# sensor_pcb_3.net
KiCad netlist of a schematic drawn in EAGLE
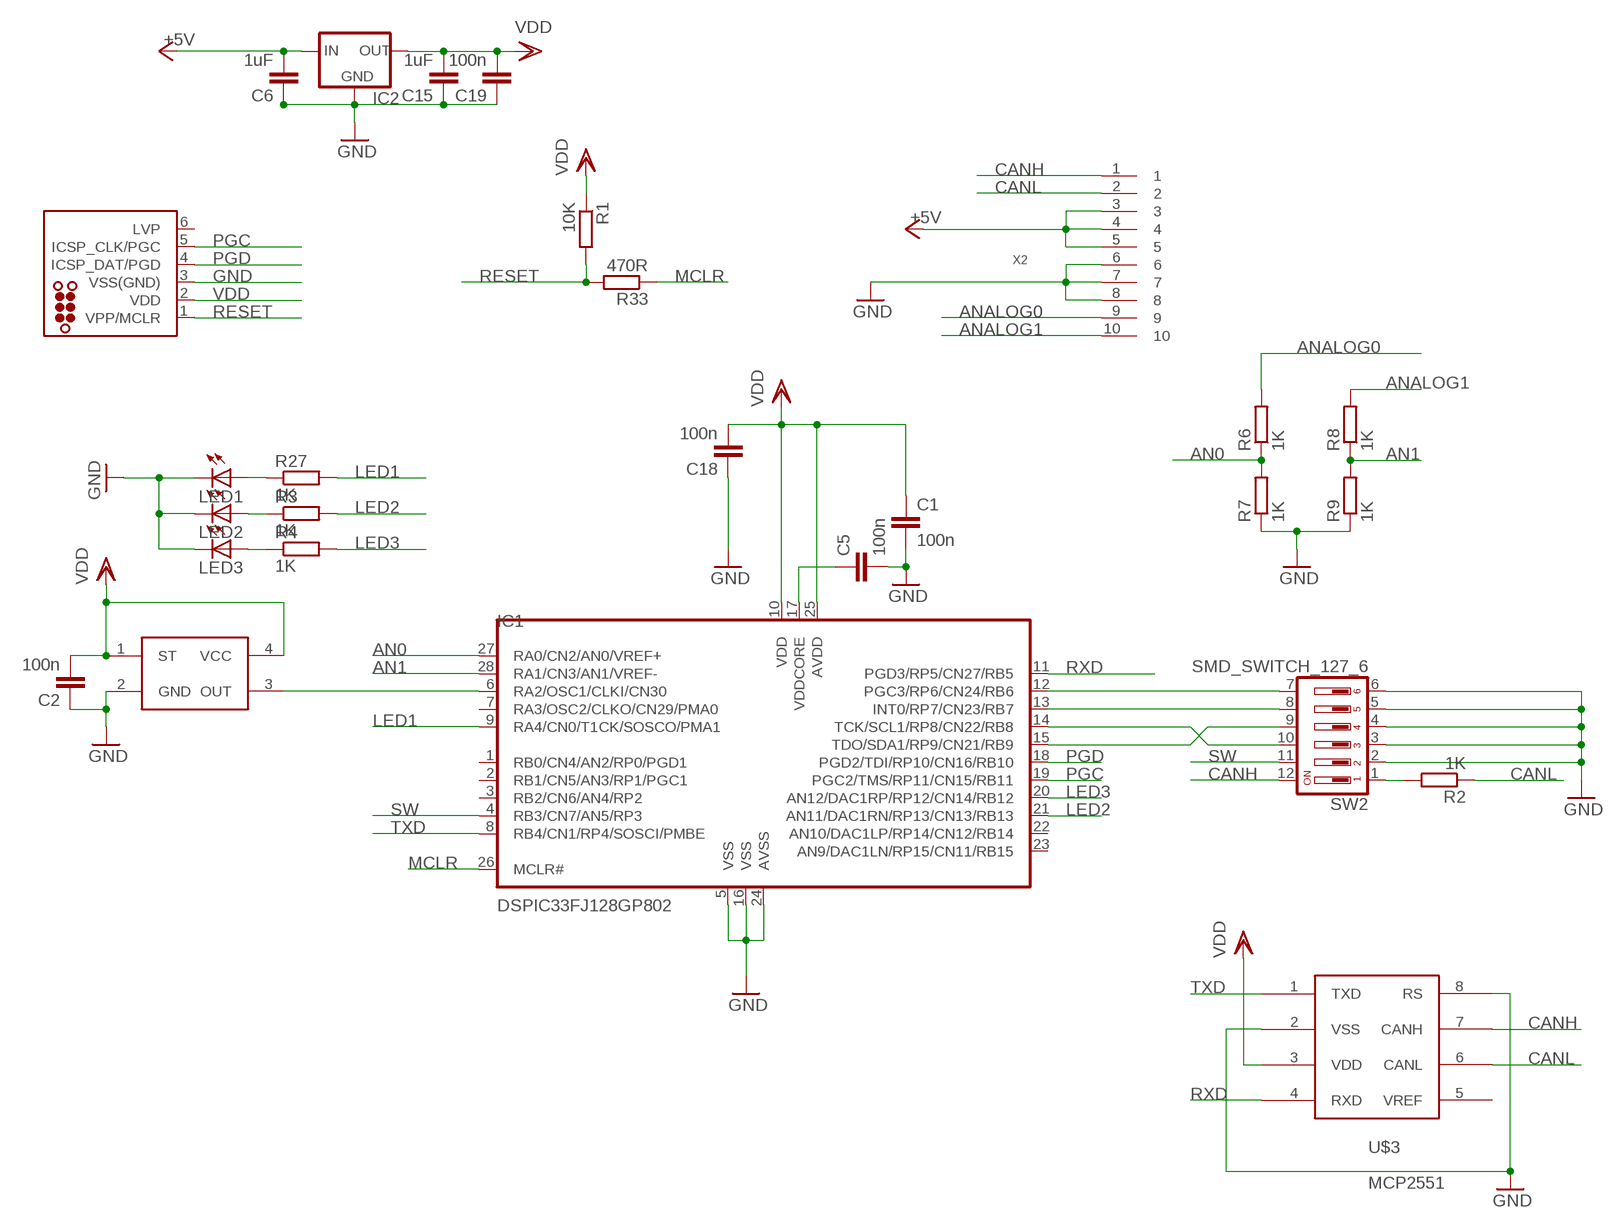
[diagram p0: schematic, sheet 1]

(export (version "E")
  (design (tool "Eeschema 10.0.6"))
  (components
    (comp (ref "C1")
      (value "100n")
      (footprint "eagle-import:C0402K")
      (libsource (lib "eagle-import") (part "C-EUC0402K"))
    )
    (comp (ref "C2")
      (value "100n")
      (footprint "eagle-import:C0402K")
      (libsource (lib "eagle-import") (part "C-EUC0402K"))
    )
    (comp (ref "C5")
      (value "100n")
      (footprint "eagle-import:C0402K")
      (libsource (lib "eagle-import") (part "C-EUC0402K"))
    )
    (comp (ref "C6")
      (value "1uF")
      (footprint "eagle-import:C0402K")
      (libsource (lib "eagle-import") (part "C-EUC0402K"))
    )
    (comp (ref "C15")
      (value "1uF")
      (footprint "eagle-import:C0402K")
      (libsource (lib "eagle-import") (part "C-EUC0402K"))
    )
    (comp (ref "C18")
      (value "100n")
      (footprint "eagle-import:C0402K")
      (libsource (lib "eagle-import") (part "C-EUC0402K"))
    )
    (comp (ref "C19")
      (value "100n")
      (footprint "eagle-import:C0402K")
      (libsource (lib "eagle-import") (part "C-EUC0402K"))
    )
    (comp (ref "IC1")
      (value "DSPIC33FJ128GP802")
      (footprint "eagle-import:QFN-S28-6X6")
      (libsource (lib "eagle-import") (part "DSPIC33FJ128GP802"))
    )
    (comp (ref "IC2")
      (value "XC63FPM")
      (footprint "eagle-import:SOT23")
      (libsource (lib "eagle-import") (part "XC63FPM"))
    )
    (comp (ref "J1")
      (value "TC2030-MCP-NL")
      (footprint "eagle-import:TC2030-MCP-NL")
      (libsource (lib "eagle-import") (part "TC2030-MCP-NL"))
    )
    (comp (ref "LED1")
      (value "LEDCHIPLED_0603")
      (footprint "eagle-import:CHIPLED_0603")
      (libsource (lib "eagle-import") (part "LEDCHIPLED_0603"))
    )
    (comp (ref "LED2")
      (value "LEDCHIPLED_0603")
      (footprint "eagle-import:CHIPLED_0603")
      (libsource (lib "eagle-import") (part "LEDCHIPLED_0603"))
    )
    (comp (ref "LED3")
      (value "LEDCHIPLED_0603")
      (footprint "eagle-import:CHIPLED_0603")
      (libsource (lib "eagle-import") (part "LEDCHIPLED_0603"))
    )
    (comp (ref "R1")
      (value "10K")
      (footprint "eagle-import:R0402")
      (libsource (lib "eagle-import") (part "R-EU_R0402"))
    )
    (comp (ref "R2")
      (value "1K")
      (footprint "eagle-import:R0402")
      (libsource (lib "eagle-import") (part "R-EU_R0402"))
    )
    (comp (ref "R3")
      (value "1K")
      (footprint "eagle-import:R0402")
      (libsource (lib "eagle-import") (part "R-EU_R0402"))
    )
    (comp (ref "R4")
      (value "1K")
      (footprint "eagle-import:R0402")
      (libsource (lib "eagle-import") (part "R-EU_R0402"))
    )
    (comp (ref "R6")
      (value "1K")
      (footprint "eagle-import:R0402")
      (libsource (lib "eagle-import") (part "R-EU_R0402"))
    )
    (comp (ref "R7")
      (value "1K")
      (footprint "eagle-import:R0402")
      (libsource (lib "eagle-import") (part "R-EU_R0402"))
    )
    (comp (ref "R8")
      (value "1K")
      (footprint "eagle-import:R0402")
      (libsource (lib "eagle-import") (part "R-EU_R0402"))
    )
    (comp (ref "R9")
      (value "1K")
      (footprint "eagle-import:R0402")
      (libsource (lib "eagle-import") (part "R-EU_R0402"))
    )
    (comp (ref "R27")
      (value "1K")
      (footprint "eagle-import:R0402")
      (libsource (lib "eagle-import") (part "R-EU_R0402"))
    )
    (comp (ref "R33")
      (value "470R")
      (footprint "eagle-import:R0402")
      (libsource (lib "eagle-import") (part "R-EU_R0402"))
    )
    (comp (ref "SW2")
      (value "SMD_SWITCH_127_6")
      (footprint "eagle-import:SMD_SWITCH_127_6")
      (libsource (lib "eagle-import") (part "SMD_SWITCH_127_6"))
    )
    (comp (ref "U$1")
      (value "SG-310")
      (footprint "eagle-import:SG-310")
      (libsource (lib "eagle-import") (part "SG-310"))
    )
    (comp (ref "U$3")
      (value "MCP2551")
      (footprint "eagle-import:999")
      (libsource (lib "eagle-import") (part "MCP2551"))
    )
    (comp (ref "X2")
      (value "10PINJAS")
      (footprint "eagle-import:10PIN0.1")
      (libsource (lib "eagle-import") (part "10PINJAS"))
    )
  )
  (nets
    (net (code "1") (name "+5V") (class "Default")
      (node (ref "C6") (pin "2") (pinfunction "2_2") (pintype "passive"))
      (node (ref "IC2") (pin "3") (pinfunction "IN_3") (pintype "input"))
      (node (ref "X2") (pin "3") (pinfunction "3_3") (pintype "bidirectional"))
      (node (ref "X2") (pin "4") (pinfunction "4_4") (pintype "bidirectional"))
      (node (ref "X2") (pin "5") (pinfunction "5_5") (pintype "bidirectional"))
    )
    (net (code "2") (name "/AN0") (class "Default")
      (node (ref "IC1") (pin "27") (pinfunction "RA0/CN2/AN0/VREF+_27") (pintype "bidirectional"))
      (node (ref "R6") (pin "1") (pinfunction "1_1") (pintype "passive"))
      (node (ref "R7") (pin "2") (pinfunction "2_2") (pintype "passive"))
    )
    (net (code "3") (name "/AN1") (class "Default")
      (node (ref "IC1") (pin "28") (pinfunction "RA1/CN3/AN1/VREF-_28") (pintype "bidirectional"))
      (node (ref "R8") (pin "1") (pinfunction "1_1") (pintype "passive"))
      (node (ref "R9") (pin "2") (pinfunction "2_2") (pintype "passive"))
    )
    (net (code "4") (name "/ANALOG0") (class "Default")
      (node (ref "R6") (pin "2") (pinfunction "2_2") (pintype "passive"))
      (node (ref "X2") (pin "9") (pinfunction "9_9") (pintype "bidirectional"))
    )
    (net (code "5") (name "/ANALOG1") (class "Default")
      (node (ref "R8") (pin "2") (pinfunction "2_2") (pintype "passive"))
      (node (ref "X2") (pin "10") (pinfunction "10_10") (pintype "bidirectional"))
    )
    (net (code "6") (name "/CANH") (class "Default")
      (node (ref "SW2") (pin "12") (pinfunction "12_12") (pintype "passive"))
      (node (ref "U$3") (pin "7") (pinfunction "CANH_7") (pintype "bidirectional"))
      (node (ref "X2") (pin "1") (pinfunction "1_1") (pintype "bidirectional"))
    )
    (net (code "7") (name "/CANL") (class "Default")
      (node (ref "R2") (pin "1") (pinfunction "1_1") (pintype "passive"))
      (node (ref "U$3") (pin "6") (pinfunction "CANL_6") (pintype "bidirectional"))
      (node (ref "X2") (pin "2") (pinfunction "2_2") (pintype "bidirectional"))
    )
    (net (code "8") (name "/LED1") (class "Default")
      (node (ref "IC1") (pin "9") (pinfunction "RA4/CN0/T1CK/SOSCO/PMA1_9") (pintype "bidirectional"))
      (node (ref "R27") (pin "2") (pinfunction "2_2") (pintype "passive"))
    )
    (net (code "9") (name "/LED2") (class "Default")
      (node (ref "IC1") (pin "21") (pinfunction "AN11/DAC1RN/RP13/CN13/RB13_21") (pintype "bidirectional"))
      (node (ref "R3") (pin "2") (pinfunction "2_2") (pintype "passive"))
    )
    (net (code "10") (name "/LED3") (class "Default")
      (node (ref "IC1") (pin "20") (pinfunction "AN12/DAC1RP/RP12/CN14/RB12_20") (pintype "bidirectional"))
      (node (ref "R4") (pin "2") (pinfunction "2_2") (pintype "passive"))
    )
    (net (code "11") (name "/MCLR") (class "Default")
      (node (ref "IC1") (pin "26") (pinfunction "MCLR#_26") (pintype "input"))
      (node (ref "R33") (pin "1") (pinfunction "1_1") (pintype "passive"))
    )
    (net (code "12") (name "/PGC") (class "Default")
      (node (ref "IC1") (pin "19") (pinfunction "PGC2/TMS/RP11/CN15/RB11_19") (pintype "bidirectional"))
      (node (ref "J1") (pin "5") (pinfunction "ICSP_CLK/PGC_5") (pintype "output"))
    )
    (net (code "13") (name "/PGD") (class "Default")
      (node (ref "IC1") (pin "18") (pinfunction "PGD2/TDI/RP10/CN16/RB10_18") (pintype "bidirectional"))
      (node (ref "J1") (pin "4") (pinfunction "ICSP_DAT/PGD_4") (pintype "bidirectional"))
    )
    (net (code "14") (name "/RESET") (class "Default")
      (node (ref "J1") (pin "1") (pinfunction "VPP/MCLR_1") (pintype "passive"))
      (node (ref "R1") (pin "2") (pinfunction "2_2") (pintype "passive"))
      (node (ref "R33") (pin "2") (pinfunction "2_2") (pintype "passive"))
    )
    (net (code "15") (name "/RXD") (class "Default")
      (node (ref "IC1") (pin "11") (pinfunction "PGD3/RP5/CN27/RB5_11") (pintype "bidirectional"))
      (node (ref "U$3") (pin "4") (pinfunction "RXD_4") (pintype "bidirectional"))
    )
    (net (code "16") (name "/SW") (class "Default")
      (node (ref "IC1") (pin "4") (pinfunction "RB3/CN7/AN5/RP3_4") (pintype "bidirectional"))
      (node (ref "SW2") (pin "11") (pinfunction "11_11") (pintype "passive"))
    )
    (net (code "17") (name "/TXD") (class "Default")
      (node (ref "IC1") (pin "8") (pinfunction "RB4/CN1/RP4/SOSCI/PMBE_8") (pintype "bidirectional"))
      (node (ref "U$3") (pin "1") (pinfunction "TXD_1") (pintype "bidirectional"))
    )
    (net (code "18") (name "GND") (class "Default")
      (node (ref "C1") (pin "2") (pinfunction "2_2") (pintype "passive"))
      (node (ref "C15") (pin "1") (pinfunction "1_1") (pintype "passive"))
      (node (ref "C18") (pin "1") (pinfunction "1_1") (pintype "passive"))
      (node (ref "C19") (pin "1") (pinfunction "1_1") (pintype "passive"))
      (node (ref "C2") (pin "1") (pinfunction "1_1") (pintype "passive"))
      (node (ref "C5") (pin "2") (pinfunction "2_2") (pintype "passive"))
      (node (ref "C6") (pin "1") (pinfunction "1_1") (pintype "passive"))
      (node (ref "IC1") (pin "16") (pinfunction "VSS_16") (pintype "power_in"))
      (node (ref "IC1") (pin "24") (pinfunction "AVSS_24") (pintype "power_in"))
      (node (ref "IC1") (pin "5") (pinfunction "VSS_5") (pintype "power_in"))
      (node (ref "IC2") (pin "1") (pinfunction "GND_1") (pintype "input"))
      (node (ref "J1") (pin "3") (pinfunction "VSS(GND)_3") (pintype "power_in"))
      (node (ref "LED1") (pin "C") (pinfunction "C_C") (pintype "passive"))
      (node (ref "LED2") (pin "C") (pinfunction "C_C") (pintype "passive"))
      (node (ref "LED3") (pin "C") (pinfunction "C_C") (pintype "passive"))
      (node (ref "R7") (pin "1") (pinfunction "1_1") (pintype "passive"))
      (node (ref "R9") (pin "1") (pinfunction "1_1") (pintype "passive"))
      (node (ref "SW2") (pin "2") (pinfunction "2_2") (pintype "passive"))
      (node (ref "SW2") (pin "3") (pinfunction "3_3") (pintype "passive"))
      (node (ref "SW2") (pin "4") (pinfunction "4_4") (pintype "passive"))
      (node (ref "SW2") (pin "5") (pinfunction "5_5") (pintype "passive"))
      (node (ref "SW2") (pin "6") (pinfunction "6_6") (pintype "passive"))
      (node (ref "U$1") (pin "2") (pinfunction "GND_2") (pintype "bidirectional"))
      (node (ref "U$3") (pin "2") (pinfunction "VSS_2") (pintype "power_in"))
      (node (ref "U$3") (pin "8") (pinfunction "RS_8") (pintype "bidirectional"))
      (node (ref "X2") (pin "6") (pinfunction "6_6") (pintype "bidirectional"))
      (node (ref "X2") (pin "7") (pinfunction "7_7") (pintype "bidirectional"))
      (node (ref "X2") (pin "8") (pinfunction "8_8") (pintype "bidirectional"))
    )
    (net (code "19") (name "Net-(IC1-INT0{slash}RP7{slash}CN23{slash}RB7)") (class "Default")
      (node (ref "IC1") (pin "13") (pinfunction "INT0/RP7/CN23/RB7_13") (pintype "bidirectional"))
      (node (ref "SW2") (pin "8") (pinfunction "8_8") (pintype "passive"))
    )
    (net (code "20") (name "Net-(IC1-PGC3{slash}RP6{slash}CN24{slash}RB6)") (class "Default")
      (node (ref "IC1") (pin "12") (pinfunction "PGC3/RP6/CN24/RB6_12") (pintype "bidirectional"))
      (node (ref "SW2") (pin "7") (pinfunction "7_7") (pintype "passive"))
    )
    (net (code "21") (name "Net-(IC1-RA2{slash}OSC1{slash}CLKI{slash}CN30)") (class "Default")
      (node (ref "IC1") (pin "6") (pinfunction "RA2/OSC1/CLKI/CN30_6") (pintype "bidirectional"))
      (node (ref "U$1") (pin "3") (pinfunction "OUT_3") (pintype "bidirectional"))
    )
    (net (code "22") (name "Net-(IC1-TCK{slash}SCL1{slash}RP8{slash}CN22{slash}RB8)") (class "Default")
      (node (ref "IC1") (pin "14") (pinfunction "TCK/SCL1/RP8/CN22/RB8_14") (pintype "bidirectional"))
      (node (ref "SW2") (pin "10") (pinfunction "10_10") (pintype "passive"))
    )
    (net (code "23") (name "Net-(IC1-TDO{slash}SDA1{slash}RP9{slash}CN21{slash}RB9)") (class "Default")
      (node (ref "IC1") (pin "15") (pinfunction "TDO/SDA1/RP9/CN21/RB9_15") (pintype "bidirectional"))
      (node (ref "SW2") (pin "9") (pinfunction "9_9") (pintype "passive"))
    )
    (net (code "24") (name "Net-(IC1-VDDCORE)") (class "Default")
      (node (ref "C5") (pin "1") (pinfunction "1_1") (pintype "passive"))
      (node (ref "IC1") (pin "17") (pinfunction "VDDCORE_17") (pintype "power_in"))
    )
    (net (code "25") (name "Net-(LED1-PadA)") (class "Default")
      (node (ref "LED1") (pin "A") (pinfunction "A_A") (pintype "passive"))
      (node (ref "R27") (pin "1") (pinfunction "1_1") (pintype "passive"))
    )
    (net (code "26") (name "Net-(LED2-PadA)") (class "Default")
      (node (ref "LED2") (pin "A") (pinfunction "A_A") (pintype "passive"))
      (node (ref "R3") (pin "1") (pinfunction "1_1") (pintype "passive"))
    )
    (net (code "27") (name "Net-(LED3-PadA)") (class "Default")
      (node (ref "LED3") (pin "A") (pinfunction "A_A") (pintype "passive"))
      (node (ref "R4") (pin "1") (pinfunction "1_1") (pintype "passive"))
    )
    (net (code "28") (name "Net-(R2-Pad2)") (class "Default")
      (node (ref "R2") (pin "2") (pinfunction "2_2") (pintype "passive"))
      (node (ref "SW2") (pin "1") (pinfunction "1_1") (pintype "passive"))
    )
    (net (code "29") (name "VDD") (class "Default")
      (node (ref "C1") (pin "1") (pinfunction "1_1") (pintype "passive"))
      (node (ref "C15") (pin "2") (pinfunction "2_2") (pintype "passive"))
      (node (ref "C18") (pin "2") (pinfunction "2_2") (pintype "passive"))
      (node (ref "C19") (pin "2") (pinfunction "2_2") (pintype "passive"))
      (node (ref "C2") (pin "2") (pinfunction "2_2") (pintype "passive"))
      (node (ref "IC1") (pin "10") (pinfunction "VDD_10") (pintype "power_in"))
      (node (ref "IC1") (pin "25") (pinfunction "AVDD_25") (pintype "power_in"))
      (node (ref "IC2") (pin "2") (pinfunction "OUT_2") (pintype "passive"))
      (node (ref "J1") (pin "2") (pinfunction "VDD_2") (pintype "power_in"))
      (node (ref "R1") (pin "1") (pinfunction "1_1") (pintype "passive"))
      (node (ref "U$1") (pin "1") (pinfunction "ST_1") (pintype "bidirectional"))
      (node (ref "U$1") (pin "4") (pinfunction "VCC_4") (pintype "bidirectional"))
      (node (ref "U$3") (pin "3") (pinfunction "VDD_3") (pintype "power_in"))
    )
    (net (code "30") (name "unconnected-(IC1-AN9{slash}DAC1LN{slash}RP15{slash}CN11{slash}RB15-Pad23)") (class "Default")
      (node (ref "IC1") (pin "23") (pinfunction "AN9/DAC1LN/RP15/CN11/RB15_23") (pintype "bidirectional"))
    )
    (net (code "31") (name "unconnected-(IC1-AN10{slash}DAC1LP{slash}RP14{slash}CN12{slash}RB14-Pad22)") (class "Default")
      (node (ref "IC1") (pin "22") (pinfunction "AN10/DAC1LP/RP14/CN12/RB14_22") (pintype "bidirectional"))
    )
    (net (code "32") (name "unconnected-(IC1-RA3{slash}OSC2{slash}CLKO{slash}CN29{slash}PMA0-Pad7)") (class "Default")
      (node (ref "IC1") (pin "7") (pinfunction "RA3/OSC2/CLKO/CN29/PMA0_7") (pintype "bidirectional"))
    )
    (net (code "33") (name "unconnected-(IC1-RB0{slash}CN4{slash}AN2{slash}RP0{slash}PGD1-Pad1)") (class "Default")
      (node (ref "IC1") (pin "1") (pinfunction "RB0/CN4/AN2/RP0/PGD1_1") (pintype "bidirectional"))
    )
    (net (code "34") (name "unconnected-(IC1-RB1{slash}CN5{slash}AN3{slash}RP1{slash}PGC1-Pad2)") (class "Default")
      (node (ref "IC1") (pin "2") (pinfunction "RB1/CN5/AN3/RP1/PGC1_2") (pintype "bidirectional"))
    )
    (net (code "35") (name "unconnected-(IC1-RB2{slash}CN6{slash}AN4{slash}RP2-Pad3)") (class "Default")
      (node (ref "IC1") (pin "3") (pinfunction "RB2/CN6/AN4/RP2_3") (pintype "bidirectional"))
    )
    (net (code "36") (name "unconnected-(J1-LVP-Pad6)") (class "Default")
      (node (ref "J1") (pin "6") (pinfunction "LVP_6") (pintype "bidirectional"))
    )
    (net (code "37") (name "unconnected-(U$3-VREF-Pad5)") (class "Default")
      (node (ref "U$3") (pin "5") (pinfunction "VREF_5") (pintype "bidirectional"))
    )
  )
)
